# LM2662.net
KiCad netlist of a schematic drawn in EAGLE
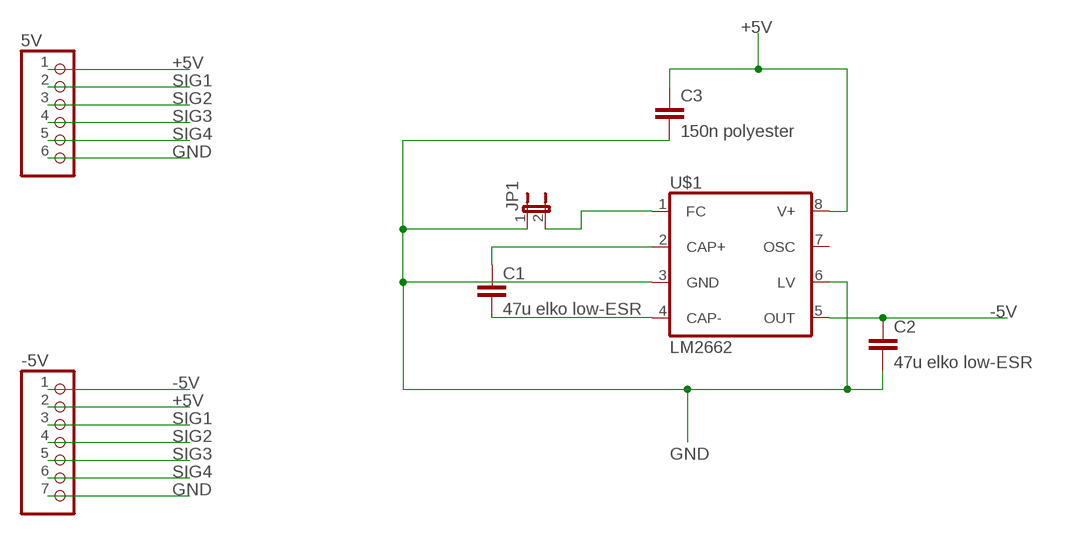
[diagram p0: schematic, sheet 1]

(export (version "E")
  (design (tool "Eeschema 10.0.6"))
  (components
    (comp (ref "-5V")
      (value "PINHD-1X7")
      (footprint "eagle-import:1X07")
      (libsource (lib "eagle-import") (part "PINHD-1X7"))
    )
    (comp (ref "5V")
      (value "PINHD-1X6")
      (footprint "eagle-import:1X06")
      (libsource (lib "eagle-import") (part "PINHD-1X6"))
    )
    (comp (ref "C1")
      (value "47u elko low-ESR")
      (footprint "eagle-import:C025-050X050")
      (libsource (lib "eagle-import") (part "C-EU025-050X050"))
    )
    (comp (ref "C2")
      (value "47u elko low-ESR")
      (footprint "eagle-import:C025-050X050")
      (libsource (lib "eagle-import") (part "C-EU025-050X050"))
    )
    (comp (ref "C3")
      (value "150n polyester")
      (footprint "eagle-import:C050-030X075")
      (libsource (lib "eagle-import") (part "C-EU050-030X075"))
    )
    (comp (ref "JP1")
      (value "JP1E")
      (footprint "eagle-import:JP1")
      (libsource (lib "eagle-import") (part "JP1E"))
    )
    (comp (ref "U$1")
      (value "LM2662")
      (footprint "eagle-import:SOIC8")
      (libsource (lib "eagle-import") (part "LM2662"))
    )
  )
  (nets
    (net (code "1") (name "/+5V") (class "Default")
      (node (ref "-5V") (pin "2") (pinfunction "2_2") (pintype "passive"))
      (node (ref "5V") (pin "1") (pinfunction "1_1") (pintype "passive"))
      (node (ref "C3") (pin "1") (pinfunction "1_1") (pintype "passive"))
      (node (ref "U$1") (pin "8") (pinfunction "V+_8") (pintype "output"))
    )
    (net (code "2") (name "/-5V") (class "Default")
      (node (ref "-5V") (pin "1") (pinfunction "1_1") (pintype "passive"))
      (node (ref "C2") (pin "1") (pinfunction "1_1") (pintype "passive"))
      (node (ref "U$1") (pin "5") (pinfunction "OUT_5") (pintype "input"))
    )
    (net (code "3") (name "/GND") (class "Default")
      (node (ref "-5V") (pin "7") (pinfunction "7_7") (pintype "passive"))
      (node (ref "5V") (pin "6") (pinfunction "6_6") (pintype "passive"))
      (node (ref "C2") (pin "2") (pinfunction "2_2") (pintype "passive"))
      (node (ref "C3") (pin "2") (pinfunction "2_2") (pintype "passive"))
      (node (ref "JP1") (pin "1") (pinfunction "1_1") (pintype "passive"))
      (node (ref "U$1") (pin "3") (pinfunction "GND_3") (pintype "input"))
      (node (ref "U$1") (pin "6") (pinfunction "LV_6") (pintype "input"))
    )
    (net (code "4") (name "/SIG1") (class "Default")
      (node (ref "-5V") (pin "3") (pinfunction "3_3") (pintype "passive"))
      (node (ref "5V") (pin "2") (pinfunction "2_2") (pintype "passive"))
    )
    (net (code "5") (name "/SIG2") (class "Default")
      (node (ref "-5V") (pin "4") (pinfunction "4_4") (pintype "passive"))
      (node (ref "5V") (pin "3") (pinfunction "3_3") (pintype "passive"))
    )
    (net (code "6") (name "/SIG3") (class "Default")
      (node (ref "-5V") (pin "5") (pinfunction "5_5") (pintype "passive"))
      (node (ref "5V") (pin "4") (pinfunction "4_4") (pintype "passive"))
    )
    (net (code "7") (name "/SIG4") (class "Default")
      (node (ref "-5V") (pin "6") (pinfunction "6_6") (pintype "passive"))
      (node (ref "5V") (pin "5") (pinfunction "5_5") (pintype "passive"))
    )
    (net (code "8") (name "Net-(U$1-CAP+)") (class "Default")
      (node (ref "C1") (pin "1") (pinfunction "1_1") (pintype "passive"))
      (node (ref "U$1") (pin "2") (pinfunction "CAP+_2") (pintype "input"))
    )
    (net (code "9") (name "Net-(U$1-CAP-)") (class "Default")
      (node (ref "C1") (pin "2") (pinfunction "2_2") (pintype "passive"))
      (node (ref "U$1") (pin "4") (pinfunction "CAP-_4") (pintype "power_in"))
    )
    (net (code "10") (name "Net-(U$1-FC)") (class "Default")
      (node (ref "JP1") (pin "2") (pinfunction "2_2") (pintype "passive"))
      (node (ref "U$1") (pin "1") (pinfunction "FC_1") (pintype "power_in"))
    )
    (net (code "11") (name "unconnected-(U$1-OSC-Pad7)") (class "Default")
      (node (ref "U$1") (pin "7") (pinfunction "OSC_7") (pintype "output"))
    )
  )
)
